# B293A_PIC32.net
KiCad netlist of a schematic drawn in Altium Designer
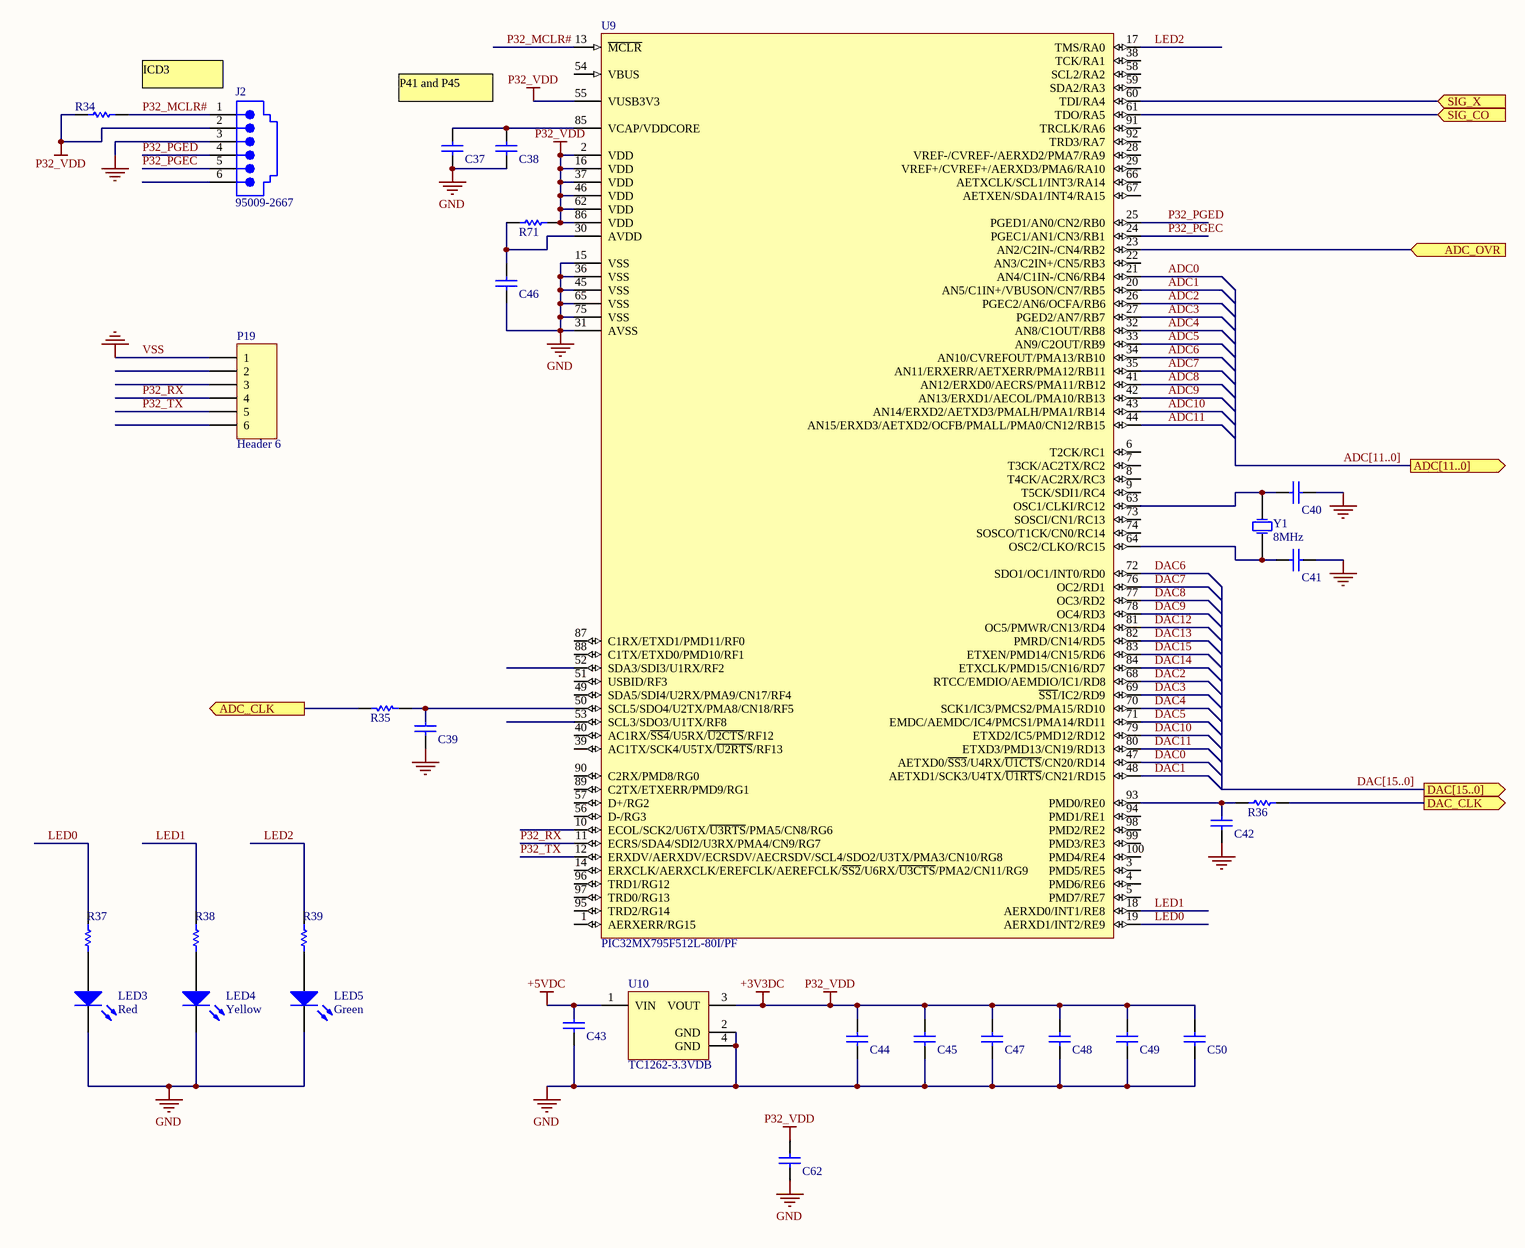
[diagram p0: B293A PIC32.SchDoc]

(export (version "E")
  (design (tool "Eeschema 10.0.6"))
  (components
    (comp (ref "C37")
      (value "CAP 10uF 25V 0805(2012)")
      (footprint "CAPC0805(2012)145_N")
      (description "CAP 10uF 25V ±20% 0805 (2012 Metric) Thickness 1.45mm SMD")
      (fields (field (name "TOLERANCE") "±20%"))
      (libsource (lib "Altium Content Vault") (part "CAP"))
    )
    (comp (ref "C38")
      (value "CAP 100nF 50V 1206(3216)")
      (footprint "CAPC1206(3216)170_L")
      (description "CAP 100nF 50V ±10% 1206 (3216 Metric) Thickness 1.7mm SMD")
      (fields (field (name "TOLERANCE") "±10%"))
      (libsource (lib "Altium Content Vault") (part "CAP"))
    )
    (comp (ref "C39")
      (value "CAP 1uF 25V 0805(2012)")
      (footprint "CAPC0805(2012)100_N")
      (description "CAP 1uF 25V ±20% 0805 (2012 Metric) Thickness 1mm SMD")
      (fields (field (name "TOLERANCE") "±20%"))
      (libsource (lib "Altium Content Vault") (part "CAP"))
    )
    (comp (ref "C40")
      (value "CAP 15pF 50V 0805(2012)")
      (footprint "CAPC0805(2012)75_L")
      (description "CAP 15pF 50V ±10% 0805 (2012 Metric) Thickness 0.75mm SMD")
      (fields (field (name "TOLERANCE") "±10%"))
      (libsource (lib "Altium Content Vault") (part "CAP"))
    )
    (comp (ref "C41")
      (value "CAP 15pF 50V 0805(2012)")
      (footprint "CAPC0805(2012)75_L")
      (description "CAP 15pF 50V ±10% 0805 (2012 Metric) Thickness 0.75mm SMD")
      (fields (field (name "TOLERANCE") "±10%"))
      (libsource (lib "Altium Content Vault") (part "CAP"))
    )
    (comp (ref "C42")
      (value "CAP 1uF 25V 0805(2012)")
      (footprint "CAPC0805(2012)100_N")
      (description "CAP 1uF 25V ±20% 0805 (2012 Metric) Thickness 1mm SMD")
      (fields (field (name "TOLERANCE") "±20%"))
      (libsource (lib "Altium Content Vault") (part "CAP"))
    )
    (comp (ref "C43")
      (value "CAP 10uF 25V 0805(2012)")
      (footprint "CAPC0805(2012)145_N")
      (description "CAP 10uF 25V ±20% 0805 (2012 Metric) Thickness 1.45mm SMD")
      (fields (field (name "TOLERANCE") "±20%"))
      (libsource (lib "Altium Content Vault") (part "CAP"))
    )
    (comp (ref "C44")
      (value "CAP 100nF 50V 0603(1608)")
      (footprint "CAPC0603(1608)100_N")
      (description "CAP 100nF 50V ±10% 0603 (1608 Metric) Thickness 1mm SMD")
      (fields (field (name "TOLERANCE") "±10%"))
      (libsource (lib "Altium Content Vault") (part "CAP"))
    )
    (comp (ref "C45")
      (value "CAP 100nF 50V 0603(1608)")
      (footprint "CAPC0603(1608)100_N")
      (description "CAP 100nF 50V ±10% 0603 (1608 Metric) Thickness 1mm SMD")
      (fields (field (name "TOLERANCE") "±10%"))
      (libsource (lib "Altium Content Vault") (part "CAP"))
    )
    (comp (ref "C46")
      (value "CAP 100nF 50V 0603(1608)")
      (footprint "CAPC0603(1608)100_N")
      (description "CAP 100nF 50V ±10% 0603 (1608 Metric) Thickness 1mm SMD")
      (fields (field (name "TOLERANCE") "±10%"))
      (libsource (lib "Altium Content Vault") (part "CAP"))
    )
    (comp (ref "C47")
      (value "CAP 100nF 50V 0603(1608)")
      (footprint "CAPC0603(1608)100_N")
      (description "CAP 100nF 50V ±10% 0603 (1608 Metric) Thickness 1mm SMD")
      (fields (field (name "TOLERANCE") "±10%"))
      (libsource (lib "Altium Content Vault") (part "CAP"))
    )
    (comp (ref "C48")
      (value "CAP 100nF 50V 0603(1608)")
      (footprint "CAPC0603(1608)100_N")
      (description "CAP 100nF 50V ±10% 0603 (1608 Metric) Thickness 1mm SMD")
      (fields (field (name "TOLERANCE") "±10%"))
      (libsource (lib "Altium Content Vault") (part "CAP"))
    )
    (comp (ref "C49")
      (value "CAP 100nF 50V 0603(1608)")
      (footprint "CAPC0603(1608)100_N")
      (description "CAP 100nF 50V ±10% 0603 (1608 Metric) Thickness 1mm SMD")
      (fields (field (name "TOLERANCE") "±10%"))
      (libsource (lib "Altium Content Vault") (part "CAP"))
    )
    (comp (ref "C50")
      (value "CAP 100nF 50V 0603(1608)")
      (footprint "CAPC0603(1608)100_N")
      (description "CAP 100nF 50V ±10% 0603 (1608 Metric) Thickness 1mm SMD")
      (fields (field (name "TOLERANCE") "±10%"))
      (libsource (lib "Altium Content Vault") (part "CAP"))
    )
    (comp (ref "C62")
      (value "CAP 47uF 25V 2220(5750)")
      (footprint "CAPC2220(5750)230_N")
      (description "CAP 47uF 25V -20% to +80% 2220 (5750 Metric) Thickness 2.2mm SMD")
      (fields (field (name "TOLERANCE") "-20% to +80%"))
      (libsource (lib "Altium Content Vault") (part "CAP"))
    )
    (comp (ref "J2")
      (value "95009-2667")
      (footprint "95009-2667")
      (description "Right Angle, Standard Profile, Flush Mount PCB Jack")
      (fields (field (name "PUBLISHER") "Altium Limited"))
      (libsource (lib "Matt SCH Library") (part "95009-2667"))
    )
    (comp (ref "LED3")
      (value "Red")
      (footprint "Matt PCB Library:1206 - LED")
      (description "LED, ALINGAP, SMD, 1206, RED")
      (fields (field (name "MANUFACTURER PART NUMBER") "KPC-3216SURCK"))
      (libsource (lib "Matt SCH Library") (part "LED 1206 RED"))
    )
    (comp (ref "LED4")
      (value "Yellow")
      (footprint "Matt PCB Library:1206 - LED")
      (description "LED, ALINGAP, SMD, 1206, YELLOW")
      (fields (field (name "MANUFACTURER PART NUMBER") "KPC-3216SYCK"))
      (libsource (lib "Matt SCH Library") (part "LED 1206 YELLOW"))
    )
    (comp (ref "LED5")
      (value "Green")
      (footprint "Matt PCB Library:1206 - LED")
      (description "LED, SMD, 1206, CLR LENS, GREEN")
      (fields (field (name "MANUFACTURER PART NUMBER") "KPC-3216SGC"))
      (libsource (lib "Matt SCH Library") (part "LED 1206 GREEN"))
    )
    (comp (ref "P19")
      (value "Header 6")
      (footprint "HDR1X6")
      (description "Header, 6-Pin")
      (fields (field (name "PUBLISHER") "Altium Limited"))
      (libsource (lib "Miscellaneous Connectors") (part "Header 6"))
    )
    (comp (ref "R34")
      (value "10K 5% 0805(2012)")
      (footprint "RESC0805(2012)_L")
      (description "10K 0.125W 5% 0805 (2012 Metric)  SMD")
      (fields (field (name "POWER") "0.125 W") (field (name "TOLERANCE") "5 %"))
      (libsource (lib "Altium Content Vault") (part "RES"))
    )
    (comp (ref "R35")
      (value "10R 5% 0805(2012)")
      (footprint "RESC0805(2012)_L")
      (description "10R 0.125W 5% 0805 (2012 Metric)  SMD")
      (fields (field (name "TOLERANCE") "5 %") (field (name "POWER") "0.125 W"))
      (libsource (lib "Altium Content Vault") (part "RES"))
    )
    (comp (ref "R36")
      (value "220R 5% 0805(2012)")
      (footprint "RESC0805(2012)_L")
      (description "220R 0.125W 5% 0805 (2012 Metric)  SMD")
      (fields (field (name "TOLERANCE") "5 %") (field (name "POWER") "0.125 W"))
      (libsource (lib "Altium Content Vault") (part "RES"))
    )
    (comp (ref "R37")
      (value "1K 5% 0805(2012)")
      (footprint "RESC0805(2012)_N")
      (description "1K 0.125W 5% 0805 (2012 Metric)  SMD")
      (fields (field (name "TOLERANCE") "5 %") (field (name "POWER") "0.125 W"))
      (libsource (lib "Altium Content Vault") (part "RES"))
    )
    (comp (ref "R38")
      (value "1K 5% 0805(2012)")
      (footprint "RESC0805(2012)_N")
      (description "1K 0.125W 5% 0805 (2012 Metric)  SMD")
      (fields (field (name "TOLERANCE") "5 %") (field (name "POWER") "0.125 W"))
      (libsource (lib "Altium Content Vault") (part "RES"))
    )
    (comp (ref "R39")
      (value "1K 5% 0805(2012)")
      (footprint "RESC0805(2012)_N")
      (description "1K 0.125W 5% 0805 (2012 Metric)  SMD")
      (fields (field (name "TOLERANCE") "5 %") (field (name "POWER") "0.125 W"))
      (libsource (lib "Altium Content Vault") (part "RES"))
    )
    (comp (ref "R71")
      (value "10R 1% 0805(2012)")
      (footprint "RESC0805(2012)_M")
      (description "10R 0.125W 1% 0805 (2012 Metric)  SMD")
      (fields (field (name "TOLERANCE") "1 %") (field (name "POWER") "0.125 W"))
      (libsource (lib "Altium Content Vault") (part "RES"))
    )
    (comp (ref "U9")
      (value "PIC32MX795F512L-80I/PF")
      (footprint "TQFP-PF100_L")
      (libsource (lib "Altium Content Vault") (part "CMP-0048-00315-1"))
    )
    (comp (ref "U10")
      (value "TC1262-3.3VDB")
      (footprint "SOT-223-DB3_L")
      (description "500mA Fixed Output CMOS LDO, 3-Pin SOT-223, Extended Temperature")
      (libsource (lib "Altium Content Vault") (part "PM-LINEREG-TC1262-IL4"))
    )
    (comp (ref "Y1")
      (value "8MHz")
      (footprint "CRYSTAL_HC49-US-SM")
      (description "CRYSTAL, 8MHZ, 16PF, SMD")
      (fields (field (name "MANUFACTURER PART NUMBER") "HC49SM-8-30-50-60-16-ATF"))
      (libsource (lib "Matt SCH Library") (part "SMD Crystal 8HMz HC-49"))
    )
  )
  (nets
    (net (code "1") (name "+3V3DC") (class "Default")
      (node (ref "C44") (pin "1") (pinfunction "1_1") (pintype "passive"))
      (node (ref "C45") (pin "1") (pinfunction "1_1") (pintype "passive"))
      (node (ref "C47") (pin "1") (pinfunction "1_1") (pintype "passive"))
      (node (ref "C48") (pin "1") (pinfunction "1_1") (pintype "passive"))
      (node (ref "C49") (pin "1") (pinfunction "1_1") (pintype "passive"))
      (node (ref "C50") (pin "1") (pinfunction "1_1") (pintype "passive"))
      (node (ref "C62") (pin "2") (pinfunction "2_2") (pintype "passive"))
      (node (ref "J2") (pin "2") (pinfunction "2_2") (pintype "passive"))
      (node (ref "R34") (pin "1") (pinfunction "1_1") (pintype "passive"))
      (node (ref "R71") (pin "2") (pinfunction "2_2") (pintype "passive"))
      (node (ref "U10") (pin "3") (pinfunction "VOUT_3") (pintype "power_in"))
      (node (ref "U9") (pin "16") (pinfunction "VDD_16") (pintype "power_in"))
      (node (ref "U9") (pin "2") (pinfunction "VDD_2") (pintype "power_in"))
      (node (ref "U9") (pin "37") (pinfunction "VDD_37") (pintype "power_in"))
      (node (ref "U9") (pin "46") (pinfunction "VDD_46") (pintype "power_in"))
      (node (ref "U9") (pin "55") (pinfunction "VUSB3V3_55") (pintype "power_in"))
      (node (ref "U9") (pin "62") (pinfunction "VDD_62") (pintype "power_in"))
      (node (ref "U9") (pin "86") (pinfunction "VDD_86") (pintype "power_in"))
    )
    (net (code "2") (name "+5VDC") (class "Default")
      (node (ref "C43") (pin "1") (pinfunction "1_1") (pintype "passive"))
      (node (ref "U10") (pin "1") (pinfunction "VIN_1") (pintype "power_in"))
    )
    (net (code "3") (name "/ADC0") (class "Default")
      (node (ref "U9") (pin "21") (pinfunction "AN4/C1IN-/CN6/RB4_21") (pintype "bidirectional"))
    )
    (net (code "4") (name "/ADC1") (class "Default")
      (node (ref "U9") (pin "20") (pinfunction "AN5/C1IN+/VBUSON/CN7/RB5_20") (pintype "bidirectional"))
    )
    (net (code "5") (name "/ADC2") (class "Default")
      (node (ref "U9") (pin "26") (pinfunction "PGEC2/AN6/OCFA/RB6_26") (pintype "bidirectional"))
    )
    (net (code "6") (name "/ADC3") (class "Default")
      (node (ref "U9") (pin "27") (pinfunction "PGED2/AN7/RB7_27") (pintype "bidirectional"))
    )
    (net (code "7") (name "/ADC4") (class "Default")
      (node (ref "U9") (pin "32") (pinfunction "AN8/C1OUT/RB8_32") (pintype "bidirectional"))
    )
    (net (code "8") (name "/ADC5") (class "Default")
      (node (ref "U9") (pin "33") (pinfunction "AN9/C2OUT/RB9_33") (pintype "bidirectional"))
    )
    (net (code "9") (name "/ADC6") (class "Default")
      (node (ref "U9") (pin "34") (pinfunction "AN10/CVREFOUT/PMA13/RB10_34") (pintype "bidirectional"))
    )
    (net (code "10") (name "/ADC7") (class "Default")
      (node (ref "U9") (pin "35") (pinfunction "AN11/ERXERR/AETXERR/PMA12/RB11_35") (pintype "bidirectional"))
    )
    (net (code "11") (name "/ADC8") (class "Default")
      (node (ref "U9") (pin "41") (pinfunction "AN12/ERXD0/AECRS/PMA11/RB12_41") (pintype "bidirectional"))
    )
    (net (code "12") (name "/ADC9") (class "Default")
      (node (ref "U9") (pin "42") (pinfunction "AN13/ERXD1/AECOL/PMA10/RB13_42") (pintype "bidirectional"))
    )
    (net (code "13") (name "/ADC10") (class "Default")
      (node (ref "U9") (pin "43") (pinfunction "AN14/ERXD2/AETXD3/PMALH/PMA1/RB14_43") (pintype "bidirectional"))
    )
    (net (code "14") (name "/ADC11") (class "Default")
      (node (ref "U9") (pin "44") (pinfunction "AN15/ERXD3/AETXD2/OCFB/PMALL/PMA0/CN12/RB15_44") (pintype "bidirectional"))
    )
    (net (code "16") (name "/ADC_CLK") (class "Default")
      (node (ref "R35") (pin "2") (pinfunction "2_2") (pintype "passive"))
    )
    (net (code "17") (name "/ADC_OVR") (class "Default")
      (node (ref "U9") (pin "23") (pinfunction "AN2/C2IN-/CN4/RB2_23") (pintype "bidirectional"))
    )
    (net (code "18") (name "/DAC0") (class "Default")
      (node (ref "U9") (pin "47") (pinfunction "AETXD0/~{SS3}/U4RX/~{U1CTS}/CN20/RD14_47") (pintype "bidirectional"))
    )
    (net (code "19") (name "/DAC1") (class "Default")
      (node (ref "U9") (pin "48") (pinfunction "AETXD1/SCK3/U4TX/~{U1RTS}/CN21/RD15_48") (pintype "bidirectional"))
    )
    (net (code "20") (name "/DAC2") (class "Default")
      (node (ref "U9") (pin "68") (pinfunction "RTCC/EMDIO/AEMDIO/IC1/RD8_68") (pintype "bidirectional"))
    )
    (net (code "21") (name "/DAC3") (class "Default")
      (node (ref "U9") (pin "69") (pinfunction "~{SS1}/IC2/RD9_69") (pintype "bidirectional"))
    )
    (net (code "22") (name "/DAC4") (class "Default")
      (node (ref "U9") (pin "70") (pinfunction "SCK1/IC3/PMCS2/PMA15/RD10_70") (pintype "bidirectional"))
    )
    (net (code "23") (name "/DAC5") (class "Default")
      (node (ref "U9") (pin "71") (pinfunction "EMDC/AEMDC/IC4/PMCS1/PMA14/RD11_71") (pintype "bidirectional"))
    )
    (net (code "24") (name "/DAC6") (class "Default")
      (node (ref "U9") (pin "72") (pinfunction "SDO1/OC1/INT0/RD0_72") (pintype "bidirectional"))
    )
    (net (code "25") (name "/DAC7") (class "Default")
      (node (ref "U9") (pin "76") (pinfunction "OC2/RD1_76") (pintype "bidirectional"))
    )
    (net (code "26") (name "/DAC8") (class "Default")
      (node (ref "U9") (pin "77") (pinfunction "OC3/RD2_77") (pintype "bidirectional"))
    )
    (net (code "27") (name "/DAC9") (class "Default")
      (node (ref "U9") (pin "78") (pinfunction "OC4/RD3_78") (pintype "bidirectional"))
    )
    (net (code "28") (name "/DAC10") (class "Default")
      (node (ref "U9") (pin "79") (pinfunction "ETXD2/IC5/PMD12/RD12_79") (pintype "bidirectional"))
    )
    (net (code "29") (name "/DAC11") (class "Default")
      (node (ref "U9") (pin "80") (pinfunction "ETXD3/PMD13/CN19/RD13_80") (pintype "bidirectional"))
    )
    (net (code "30") (name "/DAC12") (class "Default")
      (node (ref "U9") (pin "81") (pinfunction "OC5/PMWR/CN13/RD4_81") (pintype "bidirectional"))
    )
    (net (code "31") (name "/DAC13") (class "Default")
      (node (ref "U9") (pin "82") (pinfunction "PMRD/CN14/RD5_82") (pintype "bidirectional"))
    )
    (net (code "32") (name "/DAC14") (class "Default")
      (node (ref "U9") (pin "84") (pinfunction "ETXCLK/PMD15/CN16/RD7_84") (pintype "bidirectional"))
    )
    (net (code "33") (name "/DAC15") (class "Default")
      (node (ref "U9") (pin "83") (pinfunction "ETXEN/PMD14/CN15/RD6_83") (pintype "bidirectional"))
    )
    (net (code "35") (name "/DAC_CLK") (class "Default")
      (node (ref "R36") (pin "2") (pinfunction "2_2") (pintype "passive"))
    )
    (net (code "36") (name "/LED0") (class "Default")
      (node (ref "R37") (pin "2") (pinfunction "2_2") (pintype "passive"))
      (node (ref "U9") (pin "19") (pinfunction "AERXD1/INT2/RE9_19") (pintype "bidirectional"))
    )
    (net (code "37") (name "/LED1") (class "Default")
      (node (ref "R38") (pin "2") (pinfunction "2_2") (pintype "passive"))
      (node (ref "U9") (pin "18") (pinfunction "AERXD0/INT1/RE8_18") (pintype "bidirectional"))
    )
    (net (code "38") (name "/LED2") (class "Default")
      (node (ref "R39") (pin "2") (pinfunction "2_2") (pintype "passive"))
      (node (ref "U9") (pin "17") (pinfunction "TMS/RA0_17") (pintype "bidirectional"))
    )
    (net (code "39") (name "/P32_MCLR#") (class "Default")
      (node (ref "J2") (pin "1") (pinfunction "1_1") (pintype "passive"))
      (node (ref "R34") (pin "2") (pinfunction "2_2") (pintype "passive"))
      (node (ref "U9") (pin "13") (pinfunction "~{MCLR}_13") (pintype "input"))
    )
    (net (code "40") (name "/P32_PGEC") (class "Default")
      (node (ref "J2") (pin "5") (pinfunction "5_5") (pintype "passive"))
      (node (ref "U9") (pin "24") (pinfunction "PGEC1/AN1/CN3/RB1_24") (pintype "bidirectional"))
    )
    (net (code "41") (name "/P32_PGED") (class "Default")
      (node (ref "J2") (pin "4") (pinfunction "4_4") (pintype "passive"))
      (node (ref "U9") (pin "25") (pinfunction "PGED1/AN0/CN2/RB0_25") (pintype "bidirectional"))
    )
    (net (code "42") (name "/P32_RX") (class "Default")
      (node (ref "P19") (pin "4") (pinfunction "4_4") (pintype "passive"))
      (node (ref "U9") (pin "11") (pinfunction "ECRS/SDA4/SDI2/U3RX/PMA4/CN9/RG7_11") (pintype "bidirectional"))
    )
    (net (code "43") (name "/P32_TX") (class "Default")
      (node (ref "P19") (pin "5") (pinfunction "5_5") (pintype "passive"))
      (node (ref "U9") (pin "12") (pinfunction "ERXDV/AERXDV/ECRSDV/AECRSDV/SCL4/SDO2/U3TX/PMA3/CN10/RG8_12") (pintype "bidirectional"))
    )
    (net (code "44") (name "/SIG_CO") (class "Default")
      (node (ref "U9") (pin "61") (pinfunction "TDO/RA5_61") (pintype "bidirectional"))
    )
    (net (code "45") (name "/SIG_X") (class "Default")
      (node (ref "U9") (pin "60") (pinfunction "TDI/RA4_60") (pintype "bidirectional"))
    )
    (net (code "46") (name "GND") (class "Default")
      (node (ref "C37") (pin "2") (pinfunction "2_2") (pintype "passive"))
      (node (ref "C38") (pin "2") (pinfunction "2_2") (pintype "passive"))
      (node (ref "C39") (pin "2") (pinfunction "2_2") (pintype "passive"))
      (node (ref "C40") (pin "1") (pinfunction "1_1") (pintype "passive"))
      (node (ref "C41") (pin "1") (pinfunction "1_1") (pintype "passive"))
      (node (ref "C42") (pin "2") (pinfunction "2_2") (pintype "passive"))
      (node (ref "C43") (pin "2") (pinfunction "2_2") (pintype "passive"))
      (node (ref "C44") (pin "2") (pinfunction "2_2") (pintype "passive"))
      (node (ref "C45") (pin "2") (pinfunction "2_2") (pintype "passive"))
      (node (ref "C46") (pin "2") (pinfunction "2_2") (pintype "passive"))
      (node (ref "C47") (pin "2") (pinfunction "2_2") (pintype "passive"))
      (node (ref "C48") (pin "2") (pinfunction "2_2") (pintype "passive"))
      (node (ref "C49") (pin "2") (pinfunction "2_2") (pintype "passive"))
      (node (ref "C50") (pin "2") (pinfunction "2_2") (pintype "passive"))
      (node (ref "C62") (pin "1") (pinfunction "1_1") (pintype "passive"))
      (node (ref "J2") (pin "3") (pinfunction "3_3") (pintype "passive"))
      (node (ref "LED3") (pin "K") (pinfunction "K_K") (pintype "passive"))
      (node (ref "LED4") (pin "K") (pinfunction "K_K") (pintype "passive"))
      (node (ref "LED5") (pin "K") (pinfunction "K_K") (pintype "passive"))
      (node (ref "P19") (pin "1") (pinfunction "1_1") (pintype "passive"))
      (node (ref "U10") (pin "2") (pinfunction "GND_2") (pintype "power_in"))
      (node (ref "U10") (pin "4") (pinfunction "GND_4") (pintype "power_in"))
      (node (ref "U9") (pin "15") (pinfunction "VSS_15") (pintype "power_in"))
      (node (ref "U9") (pin "31") (pinfunction "AVSS_31") (pintype "power_in"))
      (node (ref "U9") (pin "36") (pinfunction "VSS_36") (pintype "power_in"))
      (node (ref "U9") (pin "45") (pinfunction "VSS_45") (pintype "power_in"))
      (node (ref "U9") (pin "65") (pinfunction "VSS_65") (pintype "power_in"))
      (node (ref "U9") (pin "75") (pinfunction "VSS_75") (pintype "power_in"))
    )
    (net (code "47") (name "Net-(LED3-PadA)") (class "Default")
      (node (ref "LED3") (pin "A") (pinfunction "A_A") (pintype "passive"))
      (node (ref "R37") (pin "1") (pinfunction "1_1") (pintype "passive"))
    )
    (net (code "48") (name "Net-(LED4-PadA)") (class "Default")
      (node (ref "LED4") (pin "A") (pinfunction "A_A") (pintype "passive"))
      (node (ref "R38") (pin "1") (pinfunction "1_1") (pintype "passive"))
    )
    (net (code "49") (name "Net-(LED5-PadA)") (class "Default")
      (node (ref "LED5") (pin "A") (pinfunction "A_A") (pintype "passive"))
      (node (ref "R39") (pin "1") (pinfunction "1_1") (pintype "passive"))
    )
    (net (code "50") (name "Net-(U9-AVDD)") (class "Default")
      (node (ref "C46") (pin "1") (pinfunction "1_1") (pintype "passive"))
      (node (ref "R71") (pin "1") (pinfunction "1_1") (pintype "passive"))
      (node (ref "U9") (pin "30") (pinfunction "AVDD_30") (pintype "power_in"))
    )
    (net (code "51") (name "Net-(U9-OSC1{slash}CLKI{slash}RC12)") (class "Default")
      (node (ref "C40") (pin "2") (pinfunction "2_2") (pintype "passive"))
      (node (ref "U9") (pin "63") (pinfunction "OSC1/CLKI/RC12_63") (pintype "bidirectional"))
      (node (ref "Y1") (pin "1") (pinfunction "OSC1_1") (pintype "passive"))
    )
    (net (code "52") (name "Net-(U9-OSC2{slash}CLKO{slash}RC15)") (class "Default")
      (node (ref "C41") (pin "2") (pinfunction "2_2") (pintype "passive"))
      (node (ref "U9") (pin "64") (pinfunction "OSC2/CLKO/RC15_64") (pintype "bidirectional"))
      (node (ref "Y1") (pin "2") (pinfunction "OSC2_2") (pintype "passive"))
    )
    (net (code "53") (name "Net-(U9-PMD0{slash}RE0)") (class "Default")
      (node (ref "C42") (pin "1") (pinfunction "1_1") (pintype "passive"))
      (node (ref "R36") (pin "1") (pinfunction "1_1") (pintype "passive"))
      (node (ref "U9") (pin "93") (pinfunction "PMD0/RE0_93") (pintype "bidirectional"))
    )
    (net (code "54") (name "Net-(U9-SCL5{slash}SDO4{slash}U2TX{slash}PMA8{slash}CN18{slash}RF5)") (class "Default")
      (node (ref "C39") (pin "1") (pinfunction "1_1") (pintype "passive"))
      (node (ref "R35") (pin "1") (pinfunction "1_1") (pintype "passive"))
      (node (ref "U9") (pin "50") (pinfunction "SCL5/SDO4/U2TX/PMA8/CN18/RF5_50") (pintype "bidirectional"))
    )
    (net (code "55") (name "Net-(U9-VCAP{slash}VDDCORE)") (class "Default")
      (node (ref "C37") (pin "1") (pinfunction "1_1") (pintype "passive"))
      (node (ref "C38") (pin "1") (pinfunction "1_1") (pintype "passive"))
      (node (ref "U9") (pin "85") (pinfunction "VCAP/VDDCORE_85") (pintype "power_in"))
    )
    (net (code "56") (name "unconnected-(J2-Pad6)") (class "Default")
      (node (ref "J2") (pin "6") (pinfunction "6_6") (pintype "passive"))
    )
    (net (code "57") (name "unconnected-(P19-Pad2)") (class "Default")
      (node (ref "P19") (pin "2") (pinfunction "2_2") (pintype "passive"))
    )
    (net (code "58") (name "unconnected-(P19-Pad3)") (class "Default")
      (node (ref "P19") (pin "3") (pinfunction "3_3") (pintype "passive"))
    )
    (net (code "59") (name "unconnected-(P19-Pad6)") (class "Default")
      (node (ref "P19") (pin "6") (pinfunction "6_6") (pintype "passive"))
    )
    (net (code "60") (name "unconnected-(U9-AC1RX{slash}~{SS4}{slash}U5RX{slash}~{U2CTS}{slash}RF12-Pad40)") (class "Default")
      (node (ref "U9") (pin "40") (pinfunction "AC1RX/~{SS4}/U5RX/~{U2CTS}/RF12_40") (pintype "bidirectional"))
    )
    (net (code "61") (name "unconnected-(U9-AC1TX{slash}SCK4{slash}U5TX{slash}~{U2RTS}{slash}RF13-Pad39)") (class "Default")
      (node (ref "U9") (pin "39") (pinfunction "AC1TX/SCK4/U5TX/~{U2RTS}/RF13_39") (pintype "bidirectional"))
    )
    (net (code "62") (name "unconnected-(U9-AERXERR{slash}RG15-Pad1)") (class "Default")
      (node (ref "U9") (pin "1") (pinfunction "AERXERR/RG15_1") (pintype "bidirectional"))
    )
    (net (code "63") (name "unconnected-(U9-AETXCLK{slash}SCL1{slash}INT3{slash}RA14-Pad66)") (class "Default")
      (node (ref "U9") (pin "66") (pinfunction "AETXCLK/SCL1/INT3/RA14_66") (pintype "bidirectional"))
    )
    (net (code "64") (name "unconnected-(U9-AETXEN{slash}SDA1{slash}INT4{slash}RA15-Pad67)") (class "Default")
      (node (ref "U9") (pin "67") (pinfunction "AETXEN/SDA1/INT4/RA15_67") (pintype "bidirectional"))
    )
    (net (code "65") (name "unconnected-(U9-AN3{slash}C2IN+{slash}CN5{slash}RB3-Pad22)") (class "Default")
      (node (ref "U9") (pin "22") (pinfunction "AN3/C2IN+/CN5/RB3_22") (pintype "bidirectional"))
    )
    (net (code "66") (name "unconnected-(U9-C1RX{slash}ETXD1{slash}PMD11{slash}RF0-Pad87)") (class "Default")
      (node (ref "U9") (pin "87") (pinfunction "C1RX/ETXD1/PMD11/RF0_87") (pintype "bidirectional"))
    )
    (net (code "67") (name "unconnected-(U9-C1TX{slash}ETXD0{slash}PMD10{slash}RF1-Pad88)") (class "Default")
      (node (ref "U9") (pin "88") (pinfunction "C1TX/ETXD0/PMD10/RF1_88") (pintype "bidirectional"))
    )
    (net (code "68") (name "unconnected-(U9-C2RX{slash}PMD8{slash}RG0-Pad90)") (class "Default")
      (node (ref "U9") (pin "90") (pinfunction "C2RX/PMD8/RG0_90") (pintype "bidirectional"))
    )
    (net (code "69") (name "unconnected-(U9-C2TX{slash}ETXERR{slash}PMD9{slash}RG1-Pad89)") (class "Default")
      (node (ref "U9") (pin "89") (pinfunction "C2TX/ETXERR/PMD9/RG1_89") (pintype "bidirectional"))
    )
    (net (code "70") (name "unconnected-(U9-D+{slash}RG2-Pad57)") (class "Default")
      (node (ref "U9") (pin "57") (pinfunction "D+/RG2_57") (pintype "bidirectional"))
    )
    (net (code "71") (name "unconnected-(U9-D-{slash}RG3-Pad56)") (class "Default")
      (node (ref "U9") (pin "56") (pinfunction "D-/RG3_56") (pintype "bidirectional"))
    )
    (net (code "72") (name "unconnected-(U9-ECOL{slash}SCK2{slash}U6TX{slash}~{U3RTS}{slash}PMA5{slash}CN8{slash}RG6-Pad10)") (class "Default")
      (node (ref "U9") (pin "10") (pinfunction "ECOL/SCK2/U6TX/~{U3RTS}/PMA5/CN8/RG6_10") (pintype "bidirectional"))
    )
    (net (code "73") (name "unconnected-(U9-ERXCLK{slash}AERXCLK{slash}EREFCLK{slash}AEREFCLK{slash}~{SS2}{slash}U6RX{slash}~{U3CTS}{slash}PMA2{slash}CN11{slash}RG9-Pad14)") (class "Default")
      (node (ref "U9") (pin "14") (pinfunction "ERXCLK/AERXCLK/EREFCLK/AEREFCLK/~{SS2}/U6RX/~{U3CTS}/PMA2/CN11/RG9_14") (pintype "bidirectional"))
    )
    (net (code "74") (name "unconnected-(U9-PMD1{slash}RE1-Pad94)") (class "Default")
      (node (ref "U9") (pin "94") (pinfunction "PMD1/RE1_94") (pintype "bidirectional"))
    )
    (net (code "75") (name "unconnected-(U9-PMD2{slash}RE2-Pad98)") (class "Default")
      (node (ref "U9") (pin "98") (pinfunction "PMD2/RE2_98") (pintype "bidirectional"))
    )
    (net (code "76") (name "unconnected-(U9-PMD3{slash}RE3-Pad99)") (class "Default")
      (node (ref "U9") (pin "99") (pinfunction "PMD3/RE3_99") (pintype "bidirectional"))
    )
    (net (code "77") (name "unconnected-(U9-PMD4{slash}RE4-Pad100)") (class "Default")
      (node (ref "U9") (pin "100") (pinfunction "PMD4/RE4_100") (pintype "bidirectional"))
    )
    (net (code "78") (name "unconnected-(U9-PMD5{slash}RE5-Pad3)") (class "Default")
      (node (ref "U9") (pin "3") (pinfunction "PMD5/RE5_3") (pintype "bidirectional"))
    )
    (net (code "79") (name "unconnected-(U9-PMD6{slash}RE6-Pad4)") (class "Default")
      (node (ref "U9") (pin "4") (pinfunction "PMD6/RE6_4") (pintype "bidirectional"))
    )
    (net (code "80") (name "unconnected-(U9-PMD7{slash}RE7-Pad5)") (class "Default")
      (node (ref "U9") (pin "5") (pinfunction "PMD7/RE7_5") (pintype "bidirectional"))
    )
    (net (code "81") (name "unconnected-(U9-SCL2{slash}RA2-Pad58)") (class "Default")
      (node (ref "U9") (pin "58") (pinfunction "SCL2/RA2_58") (pintype "bidirectional"))
    )
    (net (code "82") (name "unconnected-(U9-SCL3{slash}SDO3{slash}U1TX{slash}RF8-Pad53)") (class "Default")
      (node (ref "U9") (pin "53") (pinfunction "SCL3/SDO3/U1TX/RF8_53") (pintype "bidirectional"))
    )
    (net (code "83") (name "unconnected-(U9-SDA2{slash}RA3-Pad59)") (class "Default")
      (node (ref "U9") (pin "59") (pinfunction "SDA2/RA3_59") (pintype "bidirectional"))
    )
    (net (code "84") (name "unconnected-(U9-SDA3{slash}SDI3{slash}U1RX{slash}RF2-Pad52)") (class "Default")
      (node (ref "U9") (pin "52") (pinfunction "SDA3/SDI3/U1RX/RF2_52") (pintype "bidirectional"))
    )
    (net (code "85") (name "unconnected-(U9-SDA5{slash}SDI4{slash}U2RX{slash}PMA9{slash}CN17{slash}RF4-Pad49)") (class "Default")
      (node (ref "U9") (pin "49") (pinfunction "SDA5/SDI4/U2RX/PMA9/CN17/RF4_49") (pintype "bidirectional"))
    )
    (net (code "86") (name "unconnected-(U9-SOSCI{slash}CN1{slash}RC13-Pad73)") (class "Default")
      (node (ref "U9") (pin "73") (pinfunction "SOSCI/CN1/RC13_73") (pintype "bidirectional"))
    )
    (net (code "87") (name "unconnected-(U9-SOSCO{slash}T1CK{slash}CN0{slash}RC14-Pad74)") (class "Default")
      (node (ref "U9") (pin "74") (pinfunction "SOSCO/T1CK/CN0/RC14_74") (pintype "bidirectional"))
    )
    (net (code "88") (name "unconnected-(U9-T2CK{slash}RC1-Pad6)") (class "Default")
      (node (ref "U9") (pin "6") (pinfunction "T2CK/RC1_6") (pintype "bidirectional"))
    )
    (net (code "89") (name "unconnected-(U9-T3CK{slash}AC2TX{slash}RC2-Pad7)") (class "Default")
      (node (ref "U9") (pin "7") (pinfunction "T3CK/AC2TX/RC2_7") (pintype "bidirectional"))
    )
    (net (code "90") (name "unconnected-(U9-T4CK{slash}AC2RX{slash}RC3-Pad8)") (class "Default")
      (node (ref "U9") (pin "8") (pinfunction "T4CK/AC2RX/RC3_8") (pintype "bidirectional"))
    )
    (net (code "91") (name "unconnected-(U9-T5CK{slash}SDI1{slash}RC4-Pad9)") (class "Default")
      (node (ref "U9") (pin "9") (pinfunction "T5CK/SDI1/RC4_9") (pintype "bidirectional"))
    )
    (net (code "92") (name "unconnected-(U9-TCK{slash}RA1-Pad38)") (class "Default")
      (node (ref "U9") (pin "38") (pinfunction "TCK/RA1_38") (pintype "bidirectional"))
    )
    (net (code "93") (name "unconnected-(U9-TRCLK{slash}RA6-Pad91)") (class "Default")
      (node (ref "U9") (pin "91") (pinfunction "TRCLK/RA6_91") (pintype "bidirectional"))
    )
    (net (code "94") (name "unconnected-(U9-TRD0{slash}RG13-Pad97)") (class "Default")
      (node (ref "U9") (pin "97") (pinfunction "TRD0/RG13_97") (pintype "bidirectional"))
    )
    (net (code "95") (name "unconnected-(U9-TRD1{slash}RG12-Pad96)") (class "Default")
      (node (ref "U9") (pin "96") (pinfunction "TRD1/RG12_96") (pintype "bidirectional"))
    )
    (net (code "96") (name "unconnected-(U9-TRD2{slash}RG14-Pad95)") (class "Default")
      (node (ref "U9") (pin "95") (pinfunction "TRD2/RG14_95") (pintype "bidirectional"))
    )
    (net (code "97") (name "unconnected-(U9-TRD3{slash}RA7-Pad92)") (class "Default")
      (node (ref "U9") (pin "92") (pinfunction "TRD3/RA7_92") (pintype "bidirectional"))
    )
    (net (code "98") (name "unconnected-(U9-USBID{slash}RF3-Pad51)") (class "Default")
      (node (ref "U9") (pin "51") (pinfunction "USBID/RF3_51") (pintype "bidirectional"))
    )
    (net (code "99") (name "unconnected-(U9-VBUS-Pad54)") (class "Default")
      (node (ref "U9") (pin "54") (pinfunction "VBUS_54") (pintype "input"))
    )
    (net (code "100") (name "unconnected-(U9-VREF+{slash}CVREF+{slash}AERXD3{slash}PMA6{slash}RA10-Pad29)") (class "Default")
      (node (ref "U9") (pin "29") (pinfunction "VREF+/CVREF+/AERXD3/PMA6/RA10_29") (pintype "bidirectional"))
    )
    (net (code "101") (name "unconnected-(U9-VREF-{slash}CVREF-{slash}AERXD2{slash}PMA7{slash}RA9-Pad28)") (class "Default")
      (node (ref "U9") (pin "28") (pinfunction "VREF-/CVREF-/AERXD2/PMA7/RA9_28") (pintype "bidirectional"))
    )
  )
)
